# 1-Schematic_PCBCard.net
KiCad netlist of a schematic drawn in EasyEDA
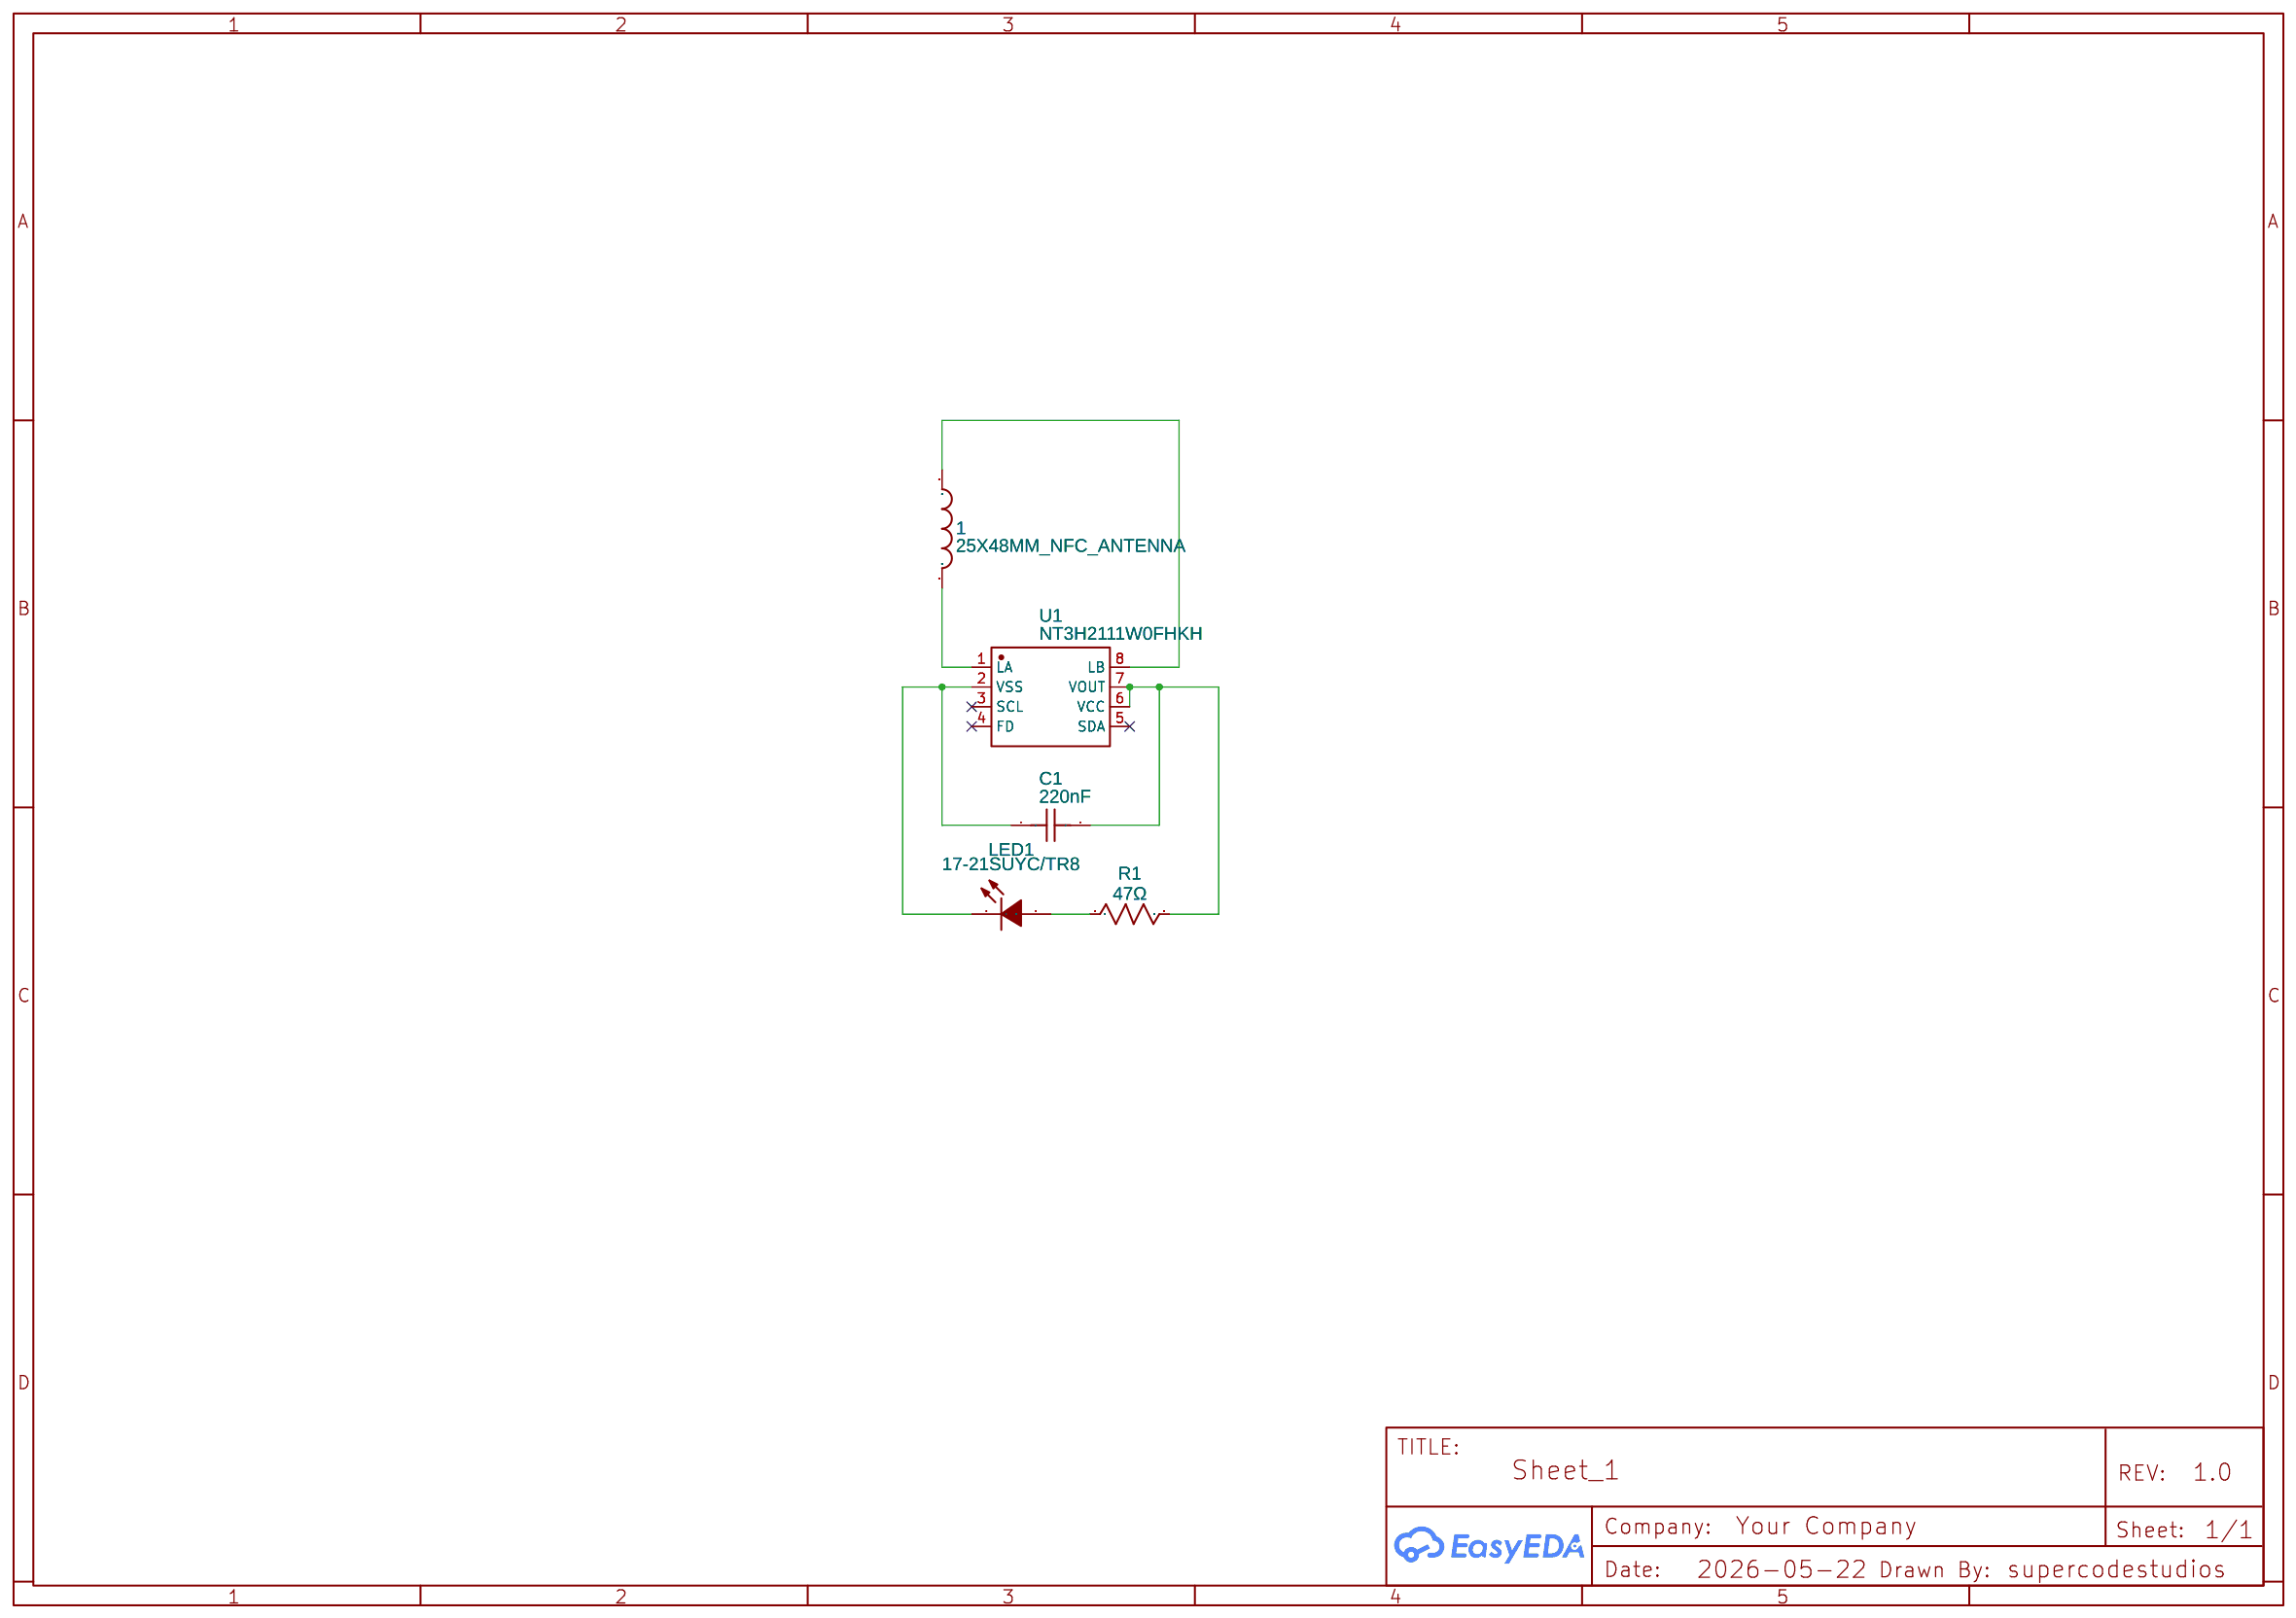
[diagram p0: schematic sheet]

(export (version "E")
  (design (tool "Eeschema 10.0.6"))
  (components
    (comp (ref "1") (value "25X48MM_NFC_ANTENNA") (libsource (lib "") (part "25X48MM_NFC_ANTENNA")))
    (comp (ref "C1") (value "220nF") (libsource (lib "") (part "C_0603_US")))
    (comp (ref "LED1")
      (value "17-21SUYC/TR8")
      (fields (field (name "Manufacturer Part") "KT-0805黄灯") (field (name "Manufacturer") "KENTO"))
      (libsource (lib "") (part "17-21SUYC/TR8"))
    )
    (comp (ref "R1") (value "47Ω") (libsource (lib "") (part "R_0603_US")))
    (comp (ref "U1")
      (value "NT3H2111W0FHKH")
      (fields (field (name "Manufacturer") "NXP(恩智浦)"))
      (libsource (lib "") (part "NT3H2111W0FHKH"))
    )
  )
  (nets
    (net (code "1") (name "Net-(LED1-+)") (class "Default")
      (node (ref "LED1") (pin "1") (pinfunction "+_1") (pintype "unspecified"))
      (node (ref "R1") (pin "1") (pinfunction "1_1") (pintype "unspecified"))
    )
    (net (code "2") (name "Net-(LED1--)") (class "Default")
      (node (ref "C1") (pin "1") (pinfunction "1_1") (pintype "unspecified"))
      (node (ref "LED1") (pin "2") (pinfunction "-_2") (pintype "unspecified"))
      (node (ref "U1") (pin "2") (pinfunction "VSS_2") (pintype "unspecified"))
    )
    (net (code "3") (name "Net-(U1-LA)") (class "Default")
      (node (ref "1") (pin "P$2") (pinfunction "P$2_P$2") (pintype "bidirectional"))
      (node (ref "U1") (pin "1") (pinfunction "LA_1") (pintype "unspecified"))
    )
    (net (code "4") (name "Net-(U1-LB)") (class "Default")
      (node (ref "1") (pin "P$1") (pinfunction "P$1_P$1") (pintype "bidirectional"))
      (node (ref "U1") (pin "8") (pinfunction "LB_8") (pintype "unspecified"))
    )
    (net (code "5") (name "Net-(U1-VCC)") (class "Default")
      (node (ref "C1") (pin "2") (pinfunction "2_2") (pintype "unspecified"))
      (node (ref "R1") (pin "2") (pinfunction "2_2") (pintype "unspecified"))
      (node (ref "U1") (pin "6") (pinfunction "VCC_6") (pintype "unspecified"))
      (node (ref "U1") (pin "7") (pinfunction "VOUT_7") (pintype "unspecified"))
    )
    (net (code "6") (name "unconnected-(U1-FD-Pad4)") (class "Default")
      (node (ref "U1") (pin "4") (pinfunction "FD_4") (pintype "unspecified+no_connect"))
    )
    (net (code "7") (name "unconnected-(U1-SCL-Pad3)") (class "Default")
      (node (ref "U1") (pin "3") (pinfunction "SCL_3") (pintype "unspecified+no_connect"))
    )
    (net (code "8") (name "unconnected-(U1-SDA-Pad5)") (class "Default")
      (node (ref "U1") (pin "5") (pinfunction "SDA_5") (pintype "unspecified+no_connect"))
    )
  )
)
